# TrinketBlinkM0I.net
KiCad netlist of a schematic drawn in EAGLE
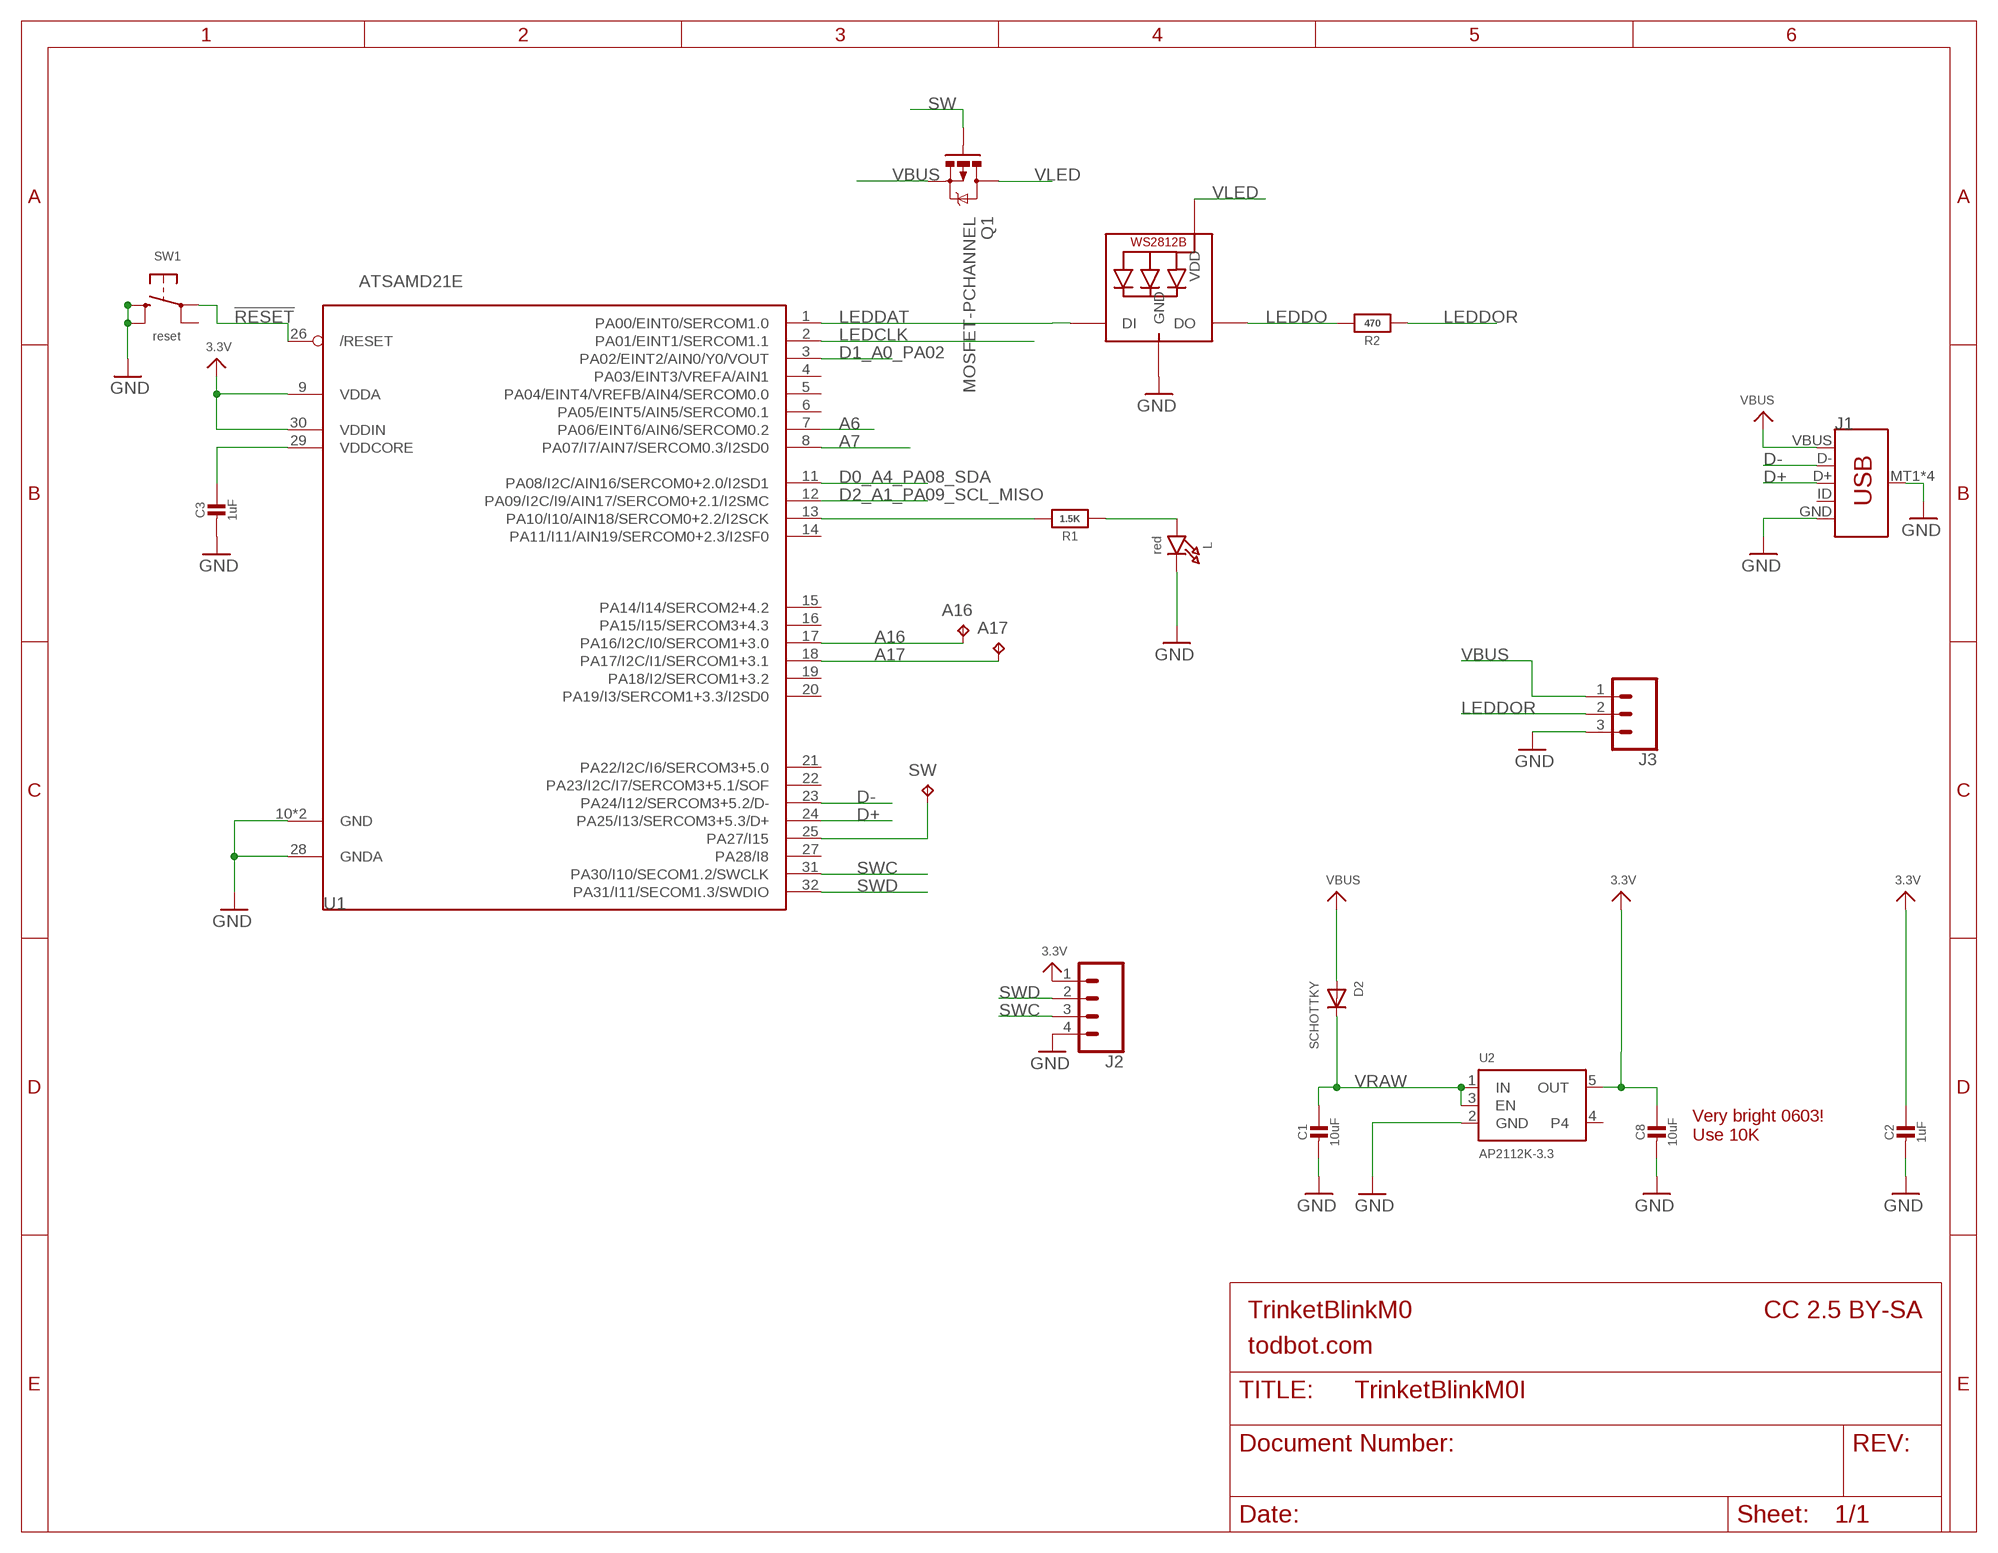
[diagram p0: schematic, sheet 1]

(export (version "E")
  (design (tool "Eeschema 10.0.6"))
  (components
    (comp (ref "A16")
      (value "TPB1,27")
      (footprint "eagle-import:B1,27")
      (libsource (lib "eagle-import") (part "TPB1,27"))
    )
    (comp (ref "A17")
      (value "TPB1,27")
      (footprint "eagle-import:B1,27")
      (libsource (lib "eagle-import") (part "TPB1,27"))
    )
    (comp (ref "C1")
      (value "10uF")
      (footprint "eagle-import:0805-NO")
      (libsource (lib "eagle-import") (part "CAP_CERAMIC0805-NOOUTLINE"))
    )
    (comp (ref "C2")
      (value "1uF")
      (footprint "eagle-import:0603-NO")
      (libsource (lib "eagle-import") (part "CAP_CERAMIC0603_NO"))
    )
    (comp (ref "C3")
      (value "1uF")
      (footprint "eagle-import:0603-NO")
      (libsource (lib "eagle-import") (part "CAP_CERAMIC0603_NO"))
    )
    (comp (ref "C8")
      (value "10uF")
      (footprint "eagle-import:0805-NO")
      (libsource (lib "eagle-import") (part "CAP_CERAMIC0805-NOOUTLINE"))
    )
    (comp (ref "D2")
      (value "SCHOTTKY")
      (footprint "eagle-import:SOD-123FL")
      (libsource (lib "eagle-import") (part "DIODE_SOD-123FL"))
    )
    (comp (ref "J1")
      (value "USB_MICRO-B_SMT")
      (footprint "eagle-import:USB-MICROB")
      (libsource (lib "eagle-import") (part "USB_MICRO-B_SMT"))
    )
    (comp (ref "J2")
      (value "CONN_04")
      (footprint "eagle-import:1X04")
      (libsource (lib "eagle-import") (part "CONN_04"))
    )
    (comp (ref "J3")
      (value "CONN_03")
      (footprint "eagle-import:1X03")
      (libsource (lib "eagle-import") (part "CONN_03"))
    )
    (comp (ref "L")
      (value "red")
      (footprint "eagle-import:CHIPLED_0603_NOOUTLINE")
      (libsource (lib "eagle-import") (part "LED0603_NOOUTLINE"))
    )
    (comp (ref "LED1")
      (value "WS2812B_5050N")
      (footprint "eagle-import:WS2812B-NARROW")
      (libsource (lib "eagle-import") (part "WS2812B_5050N"))
    )
    (comp (ref "Q1")
      (value "MOSFET-PCHANNEL")
      (footprint "eagle-import:SOT23-3")
      (libsource (lib "eagle-import") (part "MOSFET-PCHANNEL"))
    )
    (comp (ref "R1")
      (value "1.5K")
      (footprint "eagle-import:0603-NO")
      (libsource (lib "eagle-import") (part "RESISTOR_0603_NOOUT"))
    )
    (comp (ref "R2")
      (value "470")
      (footprint "eagle-import:0603-NO")
      (libsource (lib "eagle-import") (part "RESISTOR_0603_NOOUT"))
    )
    (comp (ref "SW")
      (value "TPB1,27")
      (footprint "eagle-import:B1,27")
      (libsource (lib "eagle-import") (part "TPB1,27"))
    )
    (comp (ref "SW1")
      (value "reset")
      (footprint "eagle-import:BTN_KMR2_4.6X2.8")
      (libsource (lib "eagle-import") (part "SWITCH_TACT_SMT4.6X2.8"))
    )
    (comp (ref "U1")
      (value "ATSAMD21E")
      (footprint "eagle-import:QFN32_5MM")
      (libsource (lib "eagle-import") (part "ATSAMD21E"))
    )
    (comp (ref "U2")
      (value "AP2112K-3.3")
      (footprint "eagle-import:SOT23-5")
      (libsource (lib "eagle-import") (part "VREG_SOT23-5"))
    )
  )
  (nets
    (net (code "1") (name "/A6") (class "Default")
      (node (ref "U1") (pin "7") (pinfunction "PA06/EINT6/AIN6/SERCOM0.2_7") (pintype "bidirectional"))
    )
    (net (code "2") (name "/A7") (class "Default")
      (node (ref "U1") (pin "8") (pinfunction "PA07/I7/AIN7/SERCOM0.3/I2SD0_8") (pintype "bidirectional"))
    )
    (net (code "3") (name "/A16") (class "Default")
      (node (ref "A16") (pin "TP") (pinfunction "TP_TP") (pintype "input"))
      (node (ref "U1") (pin "17") (pinfunction "PA16/I2C/I0/SERCOM1+3.0_17") (pintype "bidirectional"))
    )
    (net (code "4") (name "/A17") (class "Default")
      (node (ref "A17") (pin "TP") (pinfunction "TP_TP") (pintype "input"))
      (node (ref "U1") (pin "18") (pinfunction "PA17/I2C/I1/SERCOM1+3.1_18") (pintype "bidirectional"))
    )
    (net (code "5") (name "/D+") (class "Default")
      (node (ref "J1") (pin "D+") (pinfunction "D+_D+") (pintype "bidirectional"))
      (node (ref "U1") (pin "24") (pinfunction "PA25/I13/SERCOM3+5.3/D+_24") (pintype "bidirectional"))
    )
    (net (code "6") (name "/D-") (class "Default")
      (node (ref "J1") (pin "D-") (pinfunction "D-_D-") (pintype "bidirectional"))
      (node (ref "U1") (pin "23") (pinfunction "PA24/I12/SERCOM3+5.2/D-_23") (pintype "bidirectional"))
    )
    (net (code "7") (name "/D0_A4_PA08_SDA") (class "Default")
      (node (ref "U1") (pin "11") (pinfunction "PA08/I2C/AIN16/SERCOM0+2.0/I2SD1_11") (pintype "bidirectional"))
    )
    (net (code "8") (name "/D1_A0_PA02") (class "Default")
      (node (ref "U1") (pin "3") (pinfunction "PA02/EINT2/AIN0/Y0/VOUT_3") (pintype "bidirectional"))
    )
    (net (code "9") (name "/D2_A1_PA09_SCL_MISO") (class "Default")
      (node (ref "U1") (pin "12") (pinfunction "PA09/I2C/I9/AIN17/SERCOM0+2.1/I2SMC_12") (pintype "bidirectional"))
    )
    (net (code "10") (name "/LEDCLK") (class "Default")
      (node (ref "U1") (pin "2") (pinfunction "PA01/EINT1/SERCOM1.1_2") (pintype "bidirectional"))
    )
    (net (code "11") (name "/LEDDAT") (class "Default")
      (node (ref "LED1") (pin "4-DIN") (pinfunction "DI_4-DIN") (pintype "input"))
      (node (ref "U1") (pin "1") (pinfunction "PA00/EINT0/SERCOM1.0_1") (pintype "bidirectional"))
    )
    (net (code "12") (name "/LEDDO") (class "Default")
      (node (ref "LED1") (pin "2-DOUT") (pinfunction "DO_2-DOUT") (pintype "output"))
      (node (ref "R2") (pin "2") (pinfunction "2_2") (pintype "passive"))
    )
    (net (code "13") (name "/LEDDOR") (class "Default")
      (node (ref "J3") (pin "2") (pinfunction "2_2") (pintype "passive"))
      (node (ref "R2") (pin "1") (pinfunction "1_1") (pintype "passive"))
    )
    (net (code "14") (name "/SW") (class "Default")
      (node (ref "Q1") (pin "1") (pinfunction "G_1") (pintype "passive"))
      (node (ref "SW") (pin "TP") (pinfunction "TP_TP") (pintype "input"))
      (node (ref "U1") (pin "25") (pinfunction "PA27/I15_25") (pintype "bidirectional"))
    )
    (net (code "15") (name "/SWC") (class "Default")
      (node (ref "J2") (pin "3") (pinfunction "3_3") (pintype "passive"))
      (node (ref "U1") (pin "31") (pinfunction "PA30/I10/SECOM1.2/SWCLK_31") (pintype "bidirectional"))
    )
    (net (code "16") (name "/SWD") (class "Default")
      (node (ref "J2") (pin "2") (pinfunction "2_2") (pintype "passive"))
      (node (ref "U1") (pin "32") (pinfunction "PA31/I11/SECOM1.3/SWDIO_32") (pintype "bidirectional"))
    )
    (net (code "17") (name "/VLED") (class "Default")
      (node (ref "LED1") (pin "1-VDD") (pinfunction "VDD_1-VDD") (pintype "power_in"))
      (node (ref "Q1") (pin "3") (pinfunction "D_3") (pintype "passive"))
    )
    (net (code "18") (name "/VRAW") (class "Default")
      (node (ref "C1") (pin "1") (pinfunction "1_1") (pintype "passive"))
      (node (ref "D2") (pin "C") (pinfunction "C_C") (pintype "passive"))
      (node (ref "U2") (pin "1") (pinfunction "IN_1") (pintype "power_in"))
      (node (ref "U2") (pin "3") (pinfunction "EN_3") (pintype "input"))
    )
    (net (code "19") (name "/~{RESET}") (class "Default")
      (node (ref "SW1") (pin "A") (pinfunction "P_A") (pintype "passive"))
      (node (ref "U1") (pin "26") (pinfunction "/RESET_26") (pintype "bidirectional"))
    )
    (net (code "20") (name "3.3V") (class "Default")
      (node (ref "C2") (pin "1") (pinfunction "1_1") (pintype "passive"))
      (node (ref "C8") (pin "1") (pinfunction "1_1") (pintype "passive"))
      (node (ref "J2") (pin "1") (pinfunction "1_1") (pintype "passive"))
      (node (ref "U1") (pin "30") (pinfunction "VDDIN_30") (pintype "power_in"))
      (node (ref "U1") (pin "9") (pinfunction "VDDA_9") (pintype "power_in"))
      (node (ref "U2") (pin "5") (pinfunction "OUT_5") (pintype "power_in"))
    )
    (net (code "21") (name "GND") (class "Default")
      (node (ref "C1") (pin "2") (pinfunction "2_2") (pintype "passive"))
      (node (ref "C2") (pin "2") (pinfunction "2_2") (pintype "passive"))
      (node (ref "C3") (pin "2") (pinfunction "2_2") (pintype "passive"))
      (node (ref "C8") (pin "2") (pinfunction "2_2") (pintype "passive"))
      (node (ref "J1") (pin "GND") (pinfunction "GND_GND") (pintype "power_in"))
      (node (ref "J1") (pin "MT1") (pinfunction "SHIELD_MT1") (pintype "bidirectional"))
      (node (ref "J1") (pin "MT2") (pinfunction "SHIELD_MT2") (pintype "bidirectional"))
      (node (ref "J1") (pin "P$1") (pinfunction "SHIELD_P$1") (pintype "bidirectional"))
      (node (ref "J1") (pin "P$2") (pinfunction "SHIELD_P$2") (pintype "bidirectional"))
      (node (ref "J2") (pin "4") (pinfunction "4_4") (pintype "passive"))
      (node (ref "J3") (pin "3") (pinfunction "3_3") (pintype "passive"))
      (node (ref "L") (pin "C") (pinfunction "C_C") (pintype "passive"))
      (node (ref "LED1") (pin "3-GND") (pinfunction "GND_3-GND") (pintype "power_in"))
      (node (ref "SW1") (pin "B") (pinfunction "S_B") (pintype "passive"))
      (node (ref "SW1") (pin "B'") (pinfunction "S1_B'") (pintype "passive"))
      (node (ref "U1") (pin "10") (pinfunction "GND_10") (pintype "power_in"))
      (node (ref "U1") (pin "28") (pinfunction "GNDA_28") (pintype "power_in"))
      (node (ref "U1") (pin "33") (pinfunction "GND_33") (pintype "power_in"))
      (node (ref "U2") (pin "2") (pinfunction "GND_2") (pintype "power_in"))
    )
    (net (code "22") (name "Net-(L-PadA)") (class "Default")
      (node (ref "L") (pin "A") (pinfunction "A_A") (pintype "passive"))
      (node (ref "R1") (pin "1") (pinfunction "1_1") (pintype "passive"))
    )
    (net (code "23") (name "Net-(U1-PA10{slash}I10{slash}AIN18{slash}SERCOM0+2.2{slash}I2SCK)") (class "Default")
      (node (ref "R1") (pin "2") (pinfunction "2_2") (pintype "passive"))
      (node (ref "U1") (pin "13") (pinfunction "PA10/I10/AIN18/SERCOM0+2.2/I2SCK_13") (pintype "bidirectional"))
    )
    (net (code "24") (name "Net-(U1-VDDCORE)") (class "Default")
      (node (ref "C3") (pin "1") (pinfunction "1_1") (pintype "passive"))
      (node (ref "U1") (pin "29") (pinfunction "VDDCORE_29") (pintype "power_in"))
    )
    (net (code "25") (name "VBUS") (class "Default")
      (node (ref "D2") (pin "A") (pinfunction "A_A") (pintype "passive"))
      (node (ref "J1") (pin "VBUS") (pinfunction "VBUS_VBUS") (pintype "power_in"))
      (node (ref "J3") (pin "1") (pinfunction "1_1") (pintype "passive"))
      (node (ref "Q1") (pin "2") (pinfunction "S_2") (pintype "passive"))
    )
    (net (code "26") (name "unconnected-(J1-PadID)") (class "Default")
      (node (ref "J1") (pin "ID") (pinfunction "ID_ID") (pintype "bidirectional"))
    )
    (net (code "27") (name "unconnected-(SW1-P1-PadA')") (class "Default")
      (node (ref "SW1") (pin "A'") (pinfunction "P1_A'") (pintype "passive"))
    )
    (net (code "28") (name "unconnected-(U1-PA03{slash}EINT3{slash}VREFA{slash}AIN1-Pad4)") (class "Default")
      (node (ref "U1") (pin "4") (pinfunction "PA03/EINT3/VREFA/AIN1_4") (pintype "bidirectional"))
    )
    (net (code "29") (name "unconnected-(U1-PA04{slash}EINT4{slash}VREFB{slash}AIN4{slash}SERCOM0.0-Pad5)") (class "Default")
      (node (ref "U1") (pin "5") (pinfunction "PA04/EINT4/VREFB/AIN4/SERCOM0.0_5") (pintype "bidirectional"))
    )
    (net (code "30") (name "unconnected-(U1-PA05{slash}EINT5{slash}AIN5{slash}SERCOM0.1-Pad6)") (class "Default")
      (node (ref "U1") (pin "6") (pinfunction "PA05/EINT5/AIN5/SERCOM0.1_6") (pintype "bidirectional"))
    )
    (net (code "31") (name "unconnected-(U1-PA11{slash}I11{slash}AIN19{slash}SERCOM0+2.3{slash}I2SF0-Pad14)") (class "Default")
      (node (ref "U1") (pin "14") (pinfunction "PA11/I11/AIN19/SERCOM0+2.3/I2SF0_14") (pintype "bidirectional"))
    )
    (net (code "32") (name "unconnected-(U1-PA14{slash}I14{slash}SERCOM2+4.2-Pad15)") (class "Default")
      (node (ref "U1") (pin "15") (pinfunction "PA14/I14/SERCOM2+4.2_15") (pintype "bidirectional"))
    )
    (net (code "33") (name "unconnected-(U1-PA15{slash}I15{slash}SERCOM3+4.3-Pad16)") (class "Default")
      (node (ref "U1") (pin "16") (pinfunction "PA15/I15/SERCOM3+4.3_16") (pintype "bidirectional"))
    )
    (net (code "34") (name "unconnected-(U1-PA18{slash}I2{slash}SERCOM1+3.2-Pad19)") (class "Default")
      (node (ref "U1") (pin "19") (pinfunction "PA18/I2/SERCOM1+3.2_19") (pintype "bidirectional"))
    )
    (net (code "35") (name "unconnected-(U1-PA19{slash}I3{slash}SERCOM1+3.3{slash}I2SD0-Pad20)") (class "Default")
      (node (ref "U1") (pin "20") (pinfunction "PA19/I3/SERCOM1+3.3/I2SD0_20") (pintype "bidirectional"))
    )
    (net (code "36") (name "unconnected-(U1-PA22{slash}I2C{slash}I6{slash}SERCOM3+5.0-Pad21)") (class "Default")
      (node (ref "U1") (pin "21") (pinfunction "PA22/I2C/I6/SERCOM3+5.0_21") (pintype "bidirectional"))
    )
    (net (code "37") (name "unconnected-(U1-PA23{slash}I2C{slash}I7{slash}SERCOM3+5.1{slash}SOF-Pad22)") (class "Default")
      (node (ref "U1") (pin "22") (pinfunction "PA23/I2C/I7/SERCOM3+5.1/SOF_22") (pintype "bidirectional"))
    )
    (net (code "38") (name "unconnected-(U1-PA28{slash}I8-Pad27)") (class "Default")
      (node (ref "U1") (pin "27") (pinfunction "PA28/I8_27") (pintype "bidirectional"))
    )
    (net (code "39") (name "unconnected-(U2-P4-Pad4)") (class "Default")
      (node (ref "U2") (pin "4") (pinfunction "P4_4") (pintype "bidirectional"))
    )
  )
)
